# DuplexCable.net
KiCad netlist of a schematic drawn in EAGLE
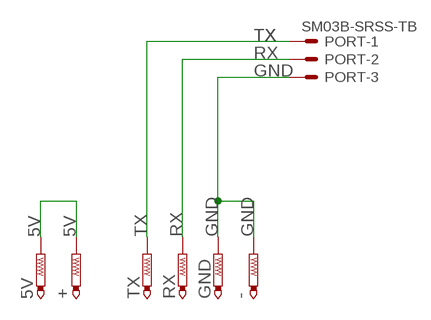
[diagram p0: schematic, sheet 1]

(export (version "E")
  (design (tool "Eeschema 10.0.6"))
  (components
    (comp (ref "+")
      (value "PTR1PAD1-13")
      (footprint "eagle-import:P1-13")
      (libsource (lib "eagle-import") (part "PTR1PAD1-13"))
    )
    (comp (ref "-")
      (value "PTR1PAD1-13")
      (footprint "eagle-import:P1-13")
      (libsource (lib "eagle-import") (part "PTR1PAD1-13"))
    )
    (comp (ref "5V")
      (value "PTR1PAD1-13")
      (footprint "eagle-import:P1-13")
      (libsource (lib "eagle-import") (part "PTR1PAD1-13"))
    )
    (comp (ref "GND")
      (value "PTR1PAD1-13")
      (footprint "eagle-import:P1-13")
      (libsource (lib "eagle-import") (part "PTR1PAD1-13"))
    )
    (comp (ref "PORT")
      (value "SM03B-SRSS-TB")
      (footprint "eagle-import:SM03B-SRSS-TB")
      (libsource (lib "eagle-import") (part "?M03B-SRSS-TBS"))
    )
    (comp (ref "RX")
      (value "PTR1PAD1-13")
      (footprint "eagle-import:P1-13")
      (libsource (lib "eagle-import") (part "PTR1PAD1-13"))
    )
    (comp (ref "TX")
      (value "PTR1PAD1-13")
      (footprint "eagle-import:P1-13")
      (libsource (lib "eagle-import") (part "PTR1PAD1-13"))
    )
  )
  (nets
    (net (code "1") (name "/5V") (class "Default")
      (node (ref "+") (pin "TP") (pinfunction "TP_TP") (pintype "input"))
      (node (ref "5V") (pin "TP") (pinfunction "TP_TP") (pintype "input"))
    )
    (net (code "2") (name "/GND") (class "Default")
      (node (ref "-") (pin "TP") (pinfunction "TP_TP") (pintype "input"))
      (node (ref "GND") (pin "TP") (pinfunction "TP_TP") (pintype "input"))
      (node (ref "PORT") (pin "3") (pinfunction "S_3") (pintype "passive"))
    )
    (net (code "3") (name "/RX") (class "Default")
      (node (ref "PORT") (pin "2") (pinfunction "S_2") (pintype "passive"))
      (node (ref "RX") (pin "TP") (pinfunction "TP_TP") (pintype "input"))
    )
    (net (code "4") (name "/TX") (class "Default")
      (node (ref "PORT") (pin "1") (pinfunction "S_1") (pintype "passive"))
      (node (ref "TX") (pin "TP") (pinfunction "TP_TP") (pintype "input"))
    )
  )
)
